# Display_Driver.net
KiCad netlist of a schematic drawn in Altium Designer
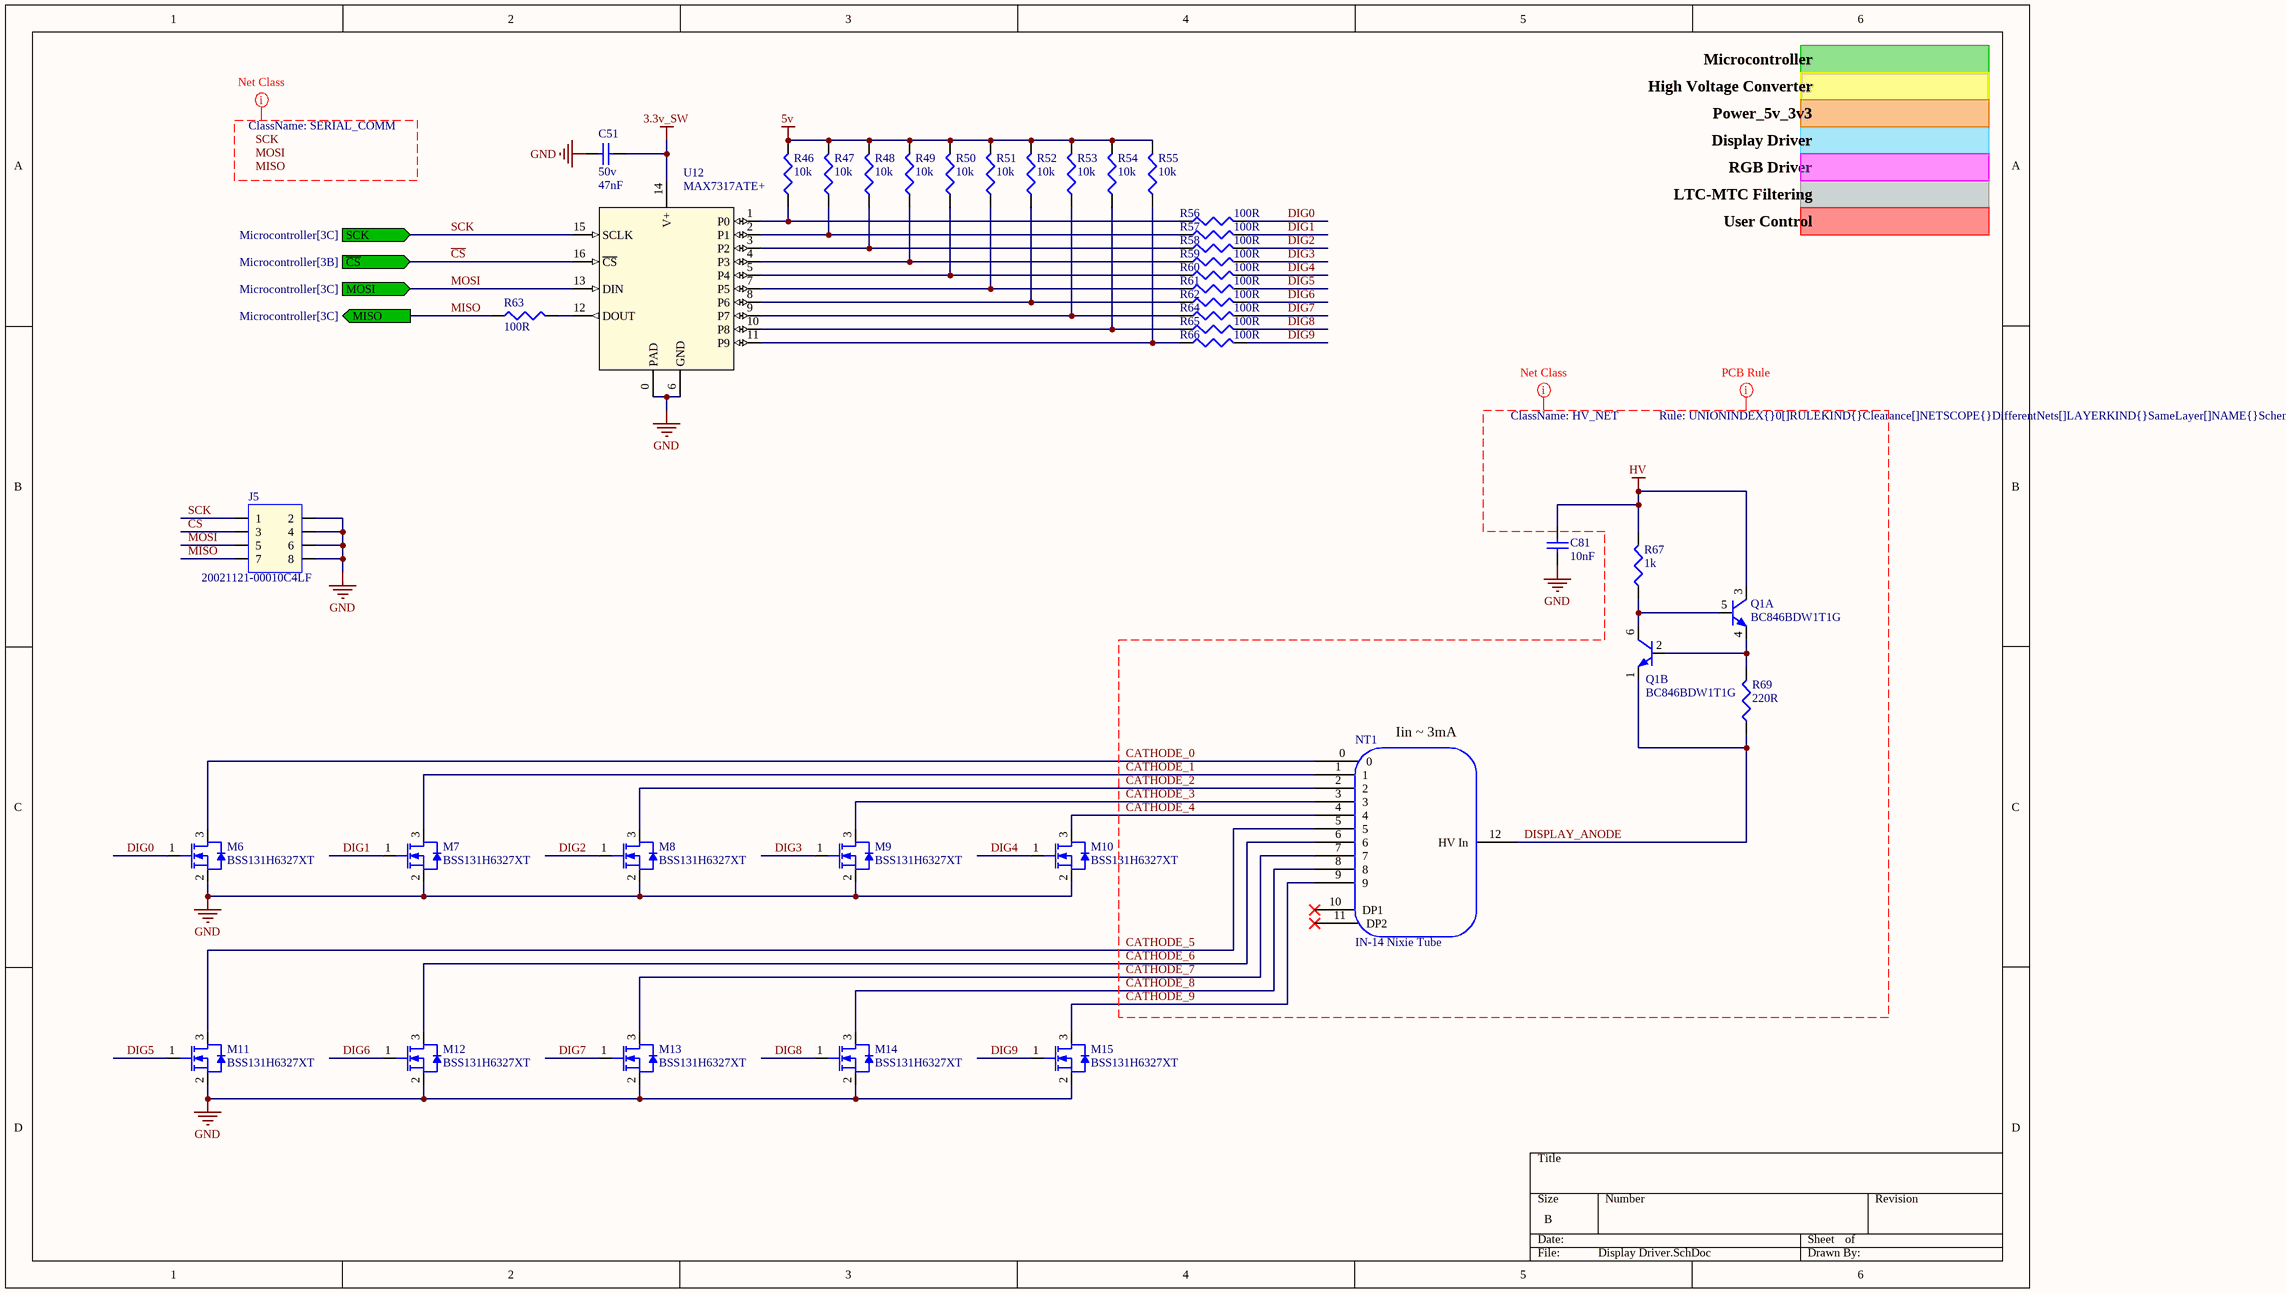
[diagram p0: Display Driver.SchDoc]

(export (version "E")
  (design (tool "Eeschema 10.0.6"))
  (components
    (comp (ref "C51")
      (value "47nF")
      (footprint "CAP0603R")
      (fields (field (name "TOLERANCE") "10%") (field (name "MFG") "VISHAY") (field (name "VOLTAGE") "50v"))
      (libsource (lib "Altium Library") (part "47nF 50v (0603)"))
    )
    (comp (ref "C81")
      (value "10nF")
      (footprint "CAP0805R")
      (fields (field (name "TOLERANCE") "10%") (field (name "MFG") "Murata") (field (name "VOLTAGE") "250v"))
      (libsource (lib "Altium Library") (part "10nF 250v (0805)"))
    )
    (comp (ref "J5")
      (value "20021121-00010C4LF")
      (footprint "2x4 SMD Header 1.27mm")
      (description "2x4 Header SMD (1.27mm)")
      (fields (field (name "MFG") "FCI"))
      (libsource (lib "Altium Library") (part "2x4 Header SMD (1.27mm)"))
    )
    (comp (ref "M6")
      (value "BSS131H6327XT")
      (footprint "SOT23-3 REFLOW")
      (description "NFET_SINGLE_100mA_240v")
      (fields (field (name "MFG") "INFINEON"))
      (libsource (lib "Altium Library") (part "BSS131H6327XT"))
    )
    (comp (ref "M7")
      (value "BSS131H6327XT")
      (footprint "SOT23-3 REFLOW")
      (description "NFET_SINGLE_100mA_240v")
      (fields (field (name "MFG") "INFINEON"))
      (libsource (lib "Altium Library") (part "BSS131H6327XT"))
    )
    (comp (ref "M8")
      (value "BSS131H6327XT")
      (footprint "SOT23-3 REFLOW")
      (description "NFET_SINGLE_100mA_240v")
      (fields (field (name "MFG") "INFINEON"))
      (libsource (lib "Altium Library") (part "BSS131H6327XT"))
    )
    (comp (ref "M9")
      (value "BSS131H6327XT")
      (footprint "SOT23-3 REFLOW")
      (description "NFET_SINGLE_100mA_240v")
      (fields (field (name "MFG") "INFINEON"))
      (libsource (lib "Altium Library") (part "BSS131H6327XT"))
    )
    (comp (ref "M10")
      (value "BSS131H6327XT")
      (footprint "SOT23-3 REFLOW")
      (description "NFET_SINGLE_100mA_240v")
      (fields (field (name "MFG") "INFINEON"))
      (libsource (lib "Altium Library") (part "BSS131H6327XT"))
    )
    (comp (ref "M11")
      (value "BSS131H6327XT")
      (footprint "SOT23-3 REFLOW")
      (description "NFET_SINGLE_100mA_240v")
      (fields (field (name "MFG") "INFINEON"))
      (libsource (lib "Altium Library") (part "BSS131H6327XT"))
    )
    (comp (ref "M12")
      (value "BSS131H6327XT")
      (footprint "SOT23-3 REFLOW")
      (description "NFET_SINGLE_100mA_240v")
      (fields (field (name "MFG") "INFINEON"))
      (libsource (lib "Altium Library") (part "BSS131H6327XT"))
    )
    (comp (ref "M13")
      (value "BSS131H6327XT")
      (footprint "SOT23-3 REFLOW")
      (description "NFET_SINGLE_100mA_240v")
      (fields (field (name "MFG") "INFINEON"))
      (libsource (lib "Altium Library") (part "BSS131H6327XT"))
    )
    (comp (ref "M14")
      (value "BSS131H6327XT")
      (footprint "SOT23-3 REFLOW")
      (description "NFET_SINGLE_100mA_240v")
      (fields (field (name "MFG") "INFINEON"))
      (libsource (lib "Altium Library") (part "BSS131H6327XT"))
    )
    (comp (ref "M15")
      (value "BSS131H6327XT")
      (footprint "SOT23-3 REFLOW")
      (description "NFET_SINGLE_100mA_240v")
      (fields (field (name "MFG") "INFINEON"))
      (libsource (lib "Altium Library") (part "BSS131H6327XT"))
    )
    (comp (ref "NT1")
      (value "IN-14 Nixie Tube")
      (footprint "IN-14 Nixie Tube")
      (libsource (lib "Altium Library") (part "IN-14 Nixie Tube"))
    )
    (comp (ref "Q1")
      (value "BC846BDW1T1G")
      (footprint "SC70")
      (description "BJT, Dual NPN, 65v, 100mA")
      (fields (field (name "MFG") "ON Semiconductor"))
      (libsource (lib "Altium Library") (part "BC846BDW1T1G"))
    )
    (comp (ref "R46")
      (value "10k")
      (footprint "RES0402R")
      (fields (field (name "TOLERANCE") "1%") (field (name "POWER") "63mW") (field (name "MFG") "Vishay"))
      (libsource (lib "Altium Library") (part "10k (0402)"))
    )
    (comp (ref "R47")
      (value "10k")
      (footprint "RES0402R")
      (fields (field (name "TOLERANCE") "1%") (field (name "POWER") "63mW") (field (name "MFG") "Vishay"))
      (libsource (lib "Altium Library") (part "10k (0402)"))
    )
    (comp (ref "R48")
      (value "10k")
      (footprint "RES0402R")
      (fields (field (name "TOLERANCE") "1%") (field (name "POWER") "63mW") (field (name "MFG") "Vishay"))
      (libsource (lib "Altium Library") (part "10k (0402)"))
    )
    (comp (ref "R49")
      (value "10k")
      (footprint "RES0402R")
      (fields (field (name "TOLERANCE") "1%") (field (name "POWER") "63mW") (field (name "MFG") "Vishay"))
      (libsource (lib "Altium Library") (part "10k (0402)"))
    )
    (comp (ref "R50")
      (value "10k")
      (footprint "RES0402R")
      (fields (field (name "TOLERANCE") "1%") (field (name "POWER") "63mW") (field (name "MFG") "Vishay"))
      (libsource (lib "Altium Library") (part "10k (0402)"))
    )
    (comp (ref "R51")
      (value "10k")
      (footprint "RES0402R")
      (fields (field (name "TOLERANCE") "1%") (field (name "POWER") "63mW") (field (name "MFG") "Vishay"))
      (libsource (lib "Altium Library") (part "10k (0402)"))
    )
    (comp (ref "R52")
      (value "10k")
      (footprint "RES0402R")
      (fields (field (name "TOLERANCE") "1%") (field (name "POWER") "63mW") (field (name "MFG") "Vishay"))
      (libsource (lib "Altium Library") (part "10k (0402)"))
    )
    (comp (ref "R53")
      (value "10k")
      (footprint "RES0402R")
      (fields (field (name "TOLERANCE") "1%") (field (name "POWER") "63mW") (field (name "MFG") "Vishay"))
      (libsource (lib "Altium Library") (part "10k (0402)"))
    )
    (comp (ref "R54")
      (value "10k")
      (footprint "RES0402R")
      (fields (field (name "TOLERANCE") "1%") (field (name "POWER") "63mW") (field (name "MFG") "Vishay"))
      (libsource (lib "Altium Library") (part "10k (0402)"))
    )
    (comp (ref "R55")
      (value "10k")
      (footprint "RES0402R")
      (fields (field (name "TOLERANCE") "1%") (field (name "POWER") "63mW") (field (name "MFG") "Vishay"))
      (libsource (lib "Altium Library") (part "10k (0402)"))
    )
    (comp (ref "R56")
      (value "100R")
      (footprint "RES0402R")
      (fields (field (name "TOLERANCE") "1%") (field (name "POWER") "63mW") (field (name "MFG") "Vishay"))
      (libsource (lib "Altium Library") (part "100R (0402)"))
    )
    (comp (ref "R57")
      (value "100R")
      (footprint "RES0402R")
      (fields (field (name "TOLERANCE") "1%") (field (name "POWER") "63mW") (field (name "MFG") "Vishay"))
      (libsource (lib "Altium Library") (part "100R (0402)"))
    )
    (comp (ref "R58")
      (value "100R")
      (footprint "RES0402R")
      (fields (field (name "TOLERANCE") "1%") (field (name "POWER") "63mW") (field (name "MFG") "Vishay"))
      (libsource (lib "Altium Library") (part "100R (0402)"))
    )
    (comp (ref "R59")
      (value "100R")
      (footprint "RES0402R")
      (fields (field (name "TOLERANCE") "1%") (field (name "POWER") "63mW") (field (name "MFG") "Vishay"))
      (libsource (lib "Altium Library") (part "100R (0402)"))
    )
    (comp (ref "R60")
      (value "100R")
      (footprint "RES0402R")
      (fields (field (name "TOLERANCE") "1%") (field (name "POWER") "63mW") (field (name "MFG") "Vishay"))
      (libsource (lib "Altium Library") (part "100R (0402)"))
    )
    (comp (ref "R61")
      (value "100R")
      (footprint "RES0402R")
      (fields (field (name "TOLERANCE") "1%") (field (name "POWER") "63mW") (field (name "MFG") "Vishay"))
      (libsource (lib "Altium Library") (part "100R (0402)"))
    )
    (comp (ref "R62")
      (value "100R")
      (footprint "RES0402R")
      (fields (field (name "TOLERANCE") "1%") (field (name "POWER") "63mW") (field (name "MFG") "Vishay"))
      (libsource (lib "Altium Library") (part "100R (0402)"))
    )
    (comp (ref "R63")
      (value "100R")
      (footprint "RES0402R")
      (fields (field (name "TOLERANCE") "1%") (field (name "POWER") "63mW") (field (name "MFG") "Vishay"))
      (libsource (lib "Altium Library") (part "100R (0402)"))
    )
    (comp (ref "R64")
      (value "100R")
      (footprint "RES0402R")
      (fields (field (name "TOLERANCE") "1%") (field (name "POWER") "63mW") (field (name "MFG") "Vishay"))
      (libsource (lib "Altium Library") (part "100R (0402)"))
    )
    (comp (ref "R65")
      (value "100R")
      (footprint "RES0402R")
      (fields (field (name "TOLERANCE") "1%") (field (name "POWER") "63mW") (field (name "MFG") "Vishay"))
      (libsource (lib "Altium Library") (part "100R (0402)"))
    )
    (comp (ref "R66")
      (value "100R")
      (footprint "RES0402R")
      (fields (field (name "TOLERANCE") "1%") (field (name "POWER") "63mW") (field (name "MFG") "Vishay"))
      (libsource (lib "Altium Library") (part "100R (0402)"))
    )
    (comp (ref "R67")
      (value "1k")
      (footprint "RES0402R")
      (fields (field (name "TOLERANCE") "1%") (field (name "POWER") "63mW") (field (name "MFG") "Vishay"))
      (libsource (lib "Altium Library") (part "1k (0402)"))
    )
    (comp (ref "R69")
      (value "220R")
      (footprint "RES0603R")
      (fields (field (name "TOLERANCE") "1%") (field (name "POWER") "0.1W") (field (name "MFG") "Vishay"))
      (libsource (lib "Altium Library") (part "220R (0603)"))
    )
    (comp (ref "U12")
      (value "MAX7317ATE+")
      (footprint "TQFN-16")
      (description "Port Expander, 10-bit, SPI")
      (fields (field (name "MFG") "MAXIM"))
      (libsource (lib "Altium Library") (part "MAX7317ATE+"))
    )
  )
  (nets
    (net (code "1") (name "/CATHODE_0") (class "Default")
      (node (ref "M6") (pin "3") (pinfunction "DRAIN_3") (pintype "passive"))
      (node (ref "NT1") (pin "0") (pinfunction "0_0") (pintype "passive"))
    )
    (net (code "2") (name "/CATHODE_1") (class "Default")
      (node (ref "M7") (pin "3") (pinfunction "DRAIN_3") (pintype "passive"))
      (node (ref "NT1") (pin "1") (pinfunction "1_1") (pintype "passive"))
    )
    (net (code "3") (name "/CATHODE_2") (class "Default")
      (node (ref "M8") (pin "3") (pinfunction "DRAIN_3") (pintype "passive"))
      (node (ref "NT1") (pin "2") (pinfunction "2_2") (pintype "passive"))
    )
    (net (code "4") (name "/CATHODE_3") (class "Default")
      (node (ref "M9") (pin "3") (pinfunction "DRAIN_3") (pintype "passive"))
      (node (ref "NT1") (pin "3") (pinfunction "3_3") (pintype "passive"))
    )
    (net (code "5") (name "/CATHODE_4") (class "Default")
      (node (ref "M10") (pin "3") (pinfunction "DRAIN_3") (pintype "passive"))
      (node (ref "NT1") (pin "4") (pinfunction "4_4") (pintype "passive"))
    )
    (net (code "6") (name "/CATHODE_5") (class "Default")
      (node (ref "M11") (pin "3") (pinfunction "DRAIN_3") (pintype "passive"))
      (node (ref "NT1") (pin "5") (pinfunction "5_5") (pintype "passive"))
    )
    (net (code "7") (name "/CATHODE_6") (class "Default")
      (node (ref "M12") (pin "3") (pinfunction "DRAIN_3") (pintype "passive"))
      (node (ref "NT1") (pin "6") (pinfunction "6_6") (pintype "passive"))
    )
    (net (code "8") (name "/CATHODE_7") (class "Default")
      (node (ref "M13") (pin "3") (pinfunction "DRAIN_3") (pintype "passive"))
      (node (ref "NT1") (pin "7") (pinfunction "7_7") (pintype "passive"))
    )
    (net (code "9") (name "/CATHODE_8") (class "Default")
      (node (ref "M14") (pin "3") (pinfunction "DRAIN_3") (pintype "passive"))
      (node (ref "NT1") (pin "8") (pinfunction "8_8") (pintype "passive"))
    )
    (net (code "10") (name "/CATHODE_9") (class "Default")
      (node (ref "M15") (pin "3") (pinfunction "DRAIN_3") (pintype "passive"))
      (node (ref "NT1") (pin "9") (pinfunction "9_9") (pintype "passive"))
    )
    (net (code "11") (name "/DIG0") (class "Default")
      (node (ref "M6") (pin "1") (pinfunction "GATE_1") (pintype "passive"))
      (node (ref "R56") (pin "2") (pinfunction "2_2") (pintype "passive"))
    )
    (net (code "12") (name "/DIG1") (class "Default")
      (node (ref "M7") (pin "1") (pinfunction "GATE_1") (pintype "passive"))
      (node (ref "R57") (pin "2") (pinfunction "2_2") (pintype "passive"))
    )
    (net (code "13") (name "/DIG2") (class "Default")
      (node (ref "M8") (pin "1") (pinfunction "GATE_1") (pintype "passive"))
      (node (ref "R58") (pin "2") (pinfunction "2_2") (pintype "passive"))
    )
    (net (code "14") (name "/DIG3") (class "Default")
      (node (ref "M9") (pin "1") (pinfunction "GATE_1") (pintype "passive"))
      (node (ref "R59") (pin "2") (pinfunction "2_2") (pintype "passive"))
    )
    (net (code "15") (name "/DIG4") (class "Default")
      (node (ref "M10") (pin "1") (pinfunction "GATE_1") (pintype "passive"))
      (node (ref "R60") (pin "2") (pinfunction "2_2") (pintype "passive"))
    )
    (net (code "16") (name "/DIG5") (class "Default")
      (node (ref "M11") (pin "1") (pinfunction "GATE_1") (pintype "passive"))
      (node (ref "R61") (pin "2") (pinfunction "2_2") (pintype "passive"))
    )
    (net (code "17") (name "/DIG6") (class "Default")
      (node (ref "M12") (pin "1") (pinfunction "GATE_1") (pintype "passive"))
      (node (ref "R62") (pin "2") (pinfunction "2_2") (pintype "passive"))
    )
    (net (code "18") (name "/DIG7") (class "Default")
      (node (ref "M13") (pin "1") (pinfunction "GATE_1") (pintype "passive"))
      (node (ref "R64") (pin "2") (pinfunction "2_2") (pintype "passive"))
    )
    (net (code "19") (name "/DIG8") (class "Default")
      (node (ref "M14") (pin "1") (pinfunction "GATE_1") (pintype "passive"))
      (node (ref "R65") (pin "2") (pinfunction "2_2") (pintype "passive"))
    )
    (net (code "20") (name "/DIG9") (class "Default")
      (node (ref "M15") (pin "1") (pinfunction "GATE_1") (pintype "passive"))
      (node (ref "R66") (pin "2") (pinfunction "2_2") (pintype "passive"))
    )
    (net (code "21") (name "/DISPLAY_ANODE") (class "Default")
      (node (ref "NT1") (pin "12") (pinfunction "HV_In_12") (pintype "passive"))
      (node (ref "Q1") (pin "1") (pinfunction "C2_1") (pintype "passive"))
      (node (ref "R69") (pin "1") (pinfunction "1_1") (pintype "passive"))
    )
    (net (code "22") (name "/MISO") (class "Default")
      (node (ref "J5") (pin "7") (pinfunction "7_7") (pintype "passive"))
      (node (ref "R63") (pin "1") (pinfunction "1_1") (pintype "passive"))
    )
    (net (code "23") (name "/MOSI") (class "Default")
      (node (ref "J5") (pin "5") (pinfunction "5_5") (pintype "passive"))
      (node (ref "U12") (pin "13") (pinfunction "DIN_13") (pintype "input"))
    )
    (net (code "24") (name "/SCK") (class "Default")
      (node (ref "J5") (pin "1") (pinfunction "1_1") (pintype "passive"))
      (node (ref "U12") (pin "15") (pinfunction "SCLK_15") (pintype "input"))
    )
    (net (code "25") (name "/~{CS}") (class "Default")
      (node (ref "J5") (pin "3") (pinfunction "3_3") (pintype "passive"))
      (node (ref "U12") (pin "16") (pinfunction "~{CS}_16") (pintype "input"))
    )
    (net (code "26") (name "3.3v_SW") (class "Default")
      (node (ref "C51") (pin "2") (pinfunction "2_2") (pintype "passive"))
      (node (ref "U12") (pin "14") (pinfunction "V+_14") (pintype "power_in"))
    )
    (net (code "27") (name "5v") (class "Default")
      (node (ref "R46") (pin "2") (pinfunction "2_2") (pintype "passive"))
      (node (ref "R47") (pin "2") (pinfunction "2_2") (pintype "passive"))
      (node (ref "R48") (pin "2") (pinfunction "2_2") (pintype "passive"))
      (node (ref "R49") (pin "2") (pinfunction "2_2") (pintype "passive"))
      (node (ref "R50") (pin "2") (pinfunction "2_2") (pintype "passive"))
      (node (ref "R51") (pin "2") (pinfunction "2_2") (pintype "passive"))
      (node (ref "R52") (pin "2") (pinfunction "2_2") (pintype "passive"))
      (node (ref "R53") (pin "2") (pinfunction "2_2") (pintype "passive"))
      (node (ref "R54") (pin "2") (pinfunction "2_2") (pintype "passive"))
      (node (ref "R55") (pin "2") (pinfunction "2_2") (pintype "passive"))
    )
    (net (code "28") (name "GND") (class "Default")
      (node (ref "C51") (pin "1") (pinfunction "1_1") (pintype "passive"))
      (node (ref "C81") (pin "2") (pinfunction "2_2") (pintype "passive"))
      (node (ref "J5") (pin "2") (pinfunction "2_2") (pintype "passive"))
      (node (ref "J5") (pin "4") (pinfunction "4_4") (pintype "passive"))
      (node (ref "J5") (pin "6") (pinfunction "6_6") (pintype "passive"))
      (node (ref "J5") (pin "8") (pinfunction "8_8") (pintype "passive"))
      (node (ref "M10") (pin "2") (pinfunction "SOURCE_2") (pintype "passive"))
      (node (ref "M11") (pin "2") (pinfunction "SOURCE_2") (pintype "passive"))
      (node (ref "M12") (pin "2") (pinfunction "SOURCE_2") (pintype "passive"))
      (node (ref "M13") (pin "2") (pinfunction "SOURCE_2") (pintype "passive"))
      (node (ref "M14") (pin "2") (pinfunction "SOURCE_2") (pintype "passive"))
      (node (ref "M15") (pin "2") (pinfunction "SOURCE_2") (pintype "passive"))
      (node (ref "M6") (pin "2") (pinfunction "SOURCE_2") (pintype "passive"))
      (node (ref "M7") (pin "2") (pinfunction "SOURCE_2") (pintype "passive"))
      (node (ref "M8") (pin "2") (pinfunction "SOURCE_2") (pintype "passive"))
      (node (ref "M9") (pin "2") (pinfunction "SOURCE_2") (pintype "passive"))
      (node (ref "U12") (pin "0") (pinfunction "PAD_0") (pintype "passive"))
      (node (ref "U12") (pin "6") (pinfunction "GND_6") (pintype "power_in"))
    )
    (net (code "29") (name "HV") (class "Default")
      (node (ref "C81") (pin "1") (pinfunction "1_1") (pintype "passive"))
      (node (ref "Q1") (pin "3") (pinfunction "E1_3") (pintype "passive"))
      (node (ref "R67") (pin "2") (pinfunction "2_2") (pintype "passive"))
    )
    (net (code "30") (name "Net-(Q1A-B1)") (class "Default")
      (node (ref "Q1") (pin "5") (pinfunction "B1_5") (pintype "passive"))
      (node (ref "Q1") (pin "6") (pinfunction "E2_6") (pintype "passive"))
      (node (ref "R67") (pin "1") (pinfunction "1_1") (pintype "passive"))
    )
    (net (code "31") (name "Net-(Q1A-C1)") (class "Default")
      (node (ref "Q1") (pin "2") (pinfunction "B2_2") (pintype "passive"))
      (node (ref "Q1") (pin "4") (pinfunction "C1_4") (pintype "passive"))
      (node (ref "R69") (pin "2") (pinfunction "2_2") (pintype "passive"))
    )
    (net (code "32") (name "Net-(U12-DOUT)") (class "Default")
      (node (ref "R63") (pin "2") (pinfunction "2_2") (pintype "passive"))
      (node (ref "U12") (pin "12") (pinfunction "DOUT_12") (pintype "output"))
    )
    (net (code "33") (name "Net-(U12-P0)") (class "Default")
      (node (ref "R46") (pin "1") (pinfunction "1_1") (pintype "passive"))
      (node (ref "R56") (pin "1") (pinfunction "1_1") (pintype "passive"))
      (node (ref "U12") (pin "1") (pinfunction "P0_1") (pintype "bidirectional"))
    )
    (net (code "34") (name "Net-(U12-P1)") (class "Default")
      (node (ref "R47") (pin "1") (pinfunction "1_1") (pintype "passive"))
      (node (ref "R57") (pin "1") (pinfunction "1_1") (pintype "passive"))
      (node (ref "U12") (pin "2") (pinfunction "P1_2") (pintype "bidirectional"))
    )
    (net (code "35") (name "Net-(U12-P2)") (class "Default")
      (node (ref "R48") (pin "1") (pinfunction "1_1") (pintype "passive"))
      (node (ref "R58") (pin "1") (pinfunction "1_1") (pintype "passive"))
      (node (ref "U12") (pin "3") (pinfunction "P2_3") (pintype "bidirectional"))
    )
    (net (code "36") (name "Net-(U12-P3)") (class "Default")
      (node (ref "R49") (pin "1") (pinfunction "1_1") (pintype "passive"))
      (node (ref "R59") (pin "1") (pinfunction "1_1") (pintype "passive"))
      (node (ref "U12") (pin "4") (pinfunction "P3_4") (pintype "bidirectional"))
    )
    (net (code "37") (name "Net-(U12-P4)") (class "Default")
      (node (ref "R50") (pin "1") (pinfunction "1_1") (pintype "passive"))
      (node (ref "R60") (pin "1") (pinfunction "1_1") (pintype "passive"))
      (node (ref "U12") (pin "5") (pinfunction "P4_5") (pintype "bidirectional"))
    )
    (net (code "38") (name "Net-(U12-P5)") (class "Default")
      (node (ref "R51") (pin "1") (pinfunction "1_1") (pintype "passive"))
      (node (ref "R61") (pin "1") (pinfunction "1_1") (pintype "passive"))
      (node (ref "U12") (pin "7") (pinfunction "P5_7") (pintype "bidirectional"))
    )
    (net (code "39") (name "Net-(U12-P6)") (class "Default")
      (node (ref "R52") (pin "1") (pinfunction "1_1") (pintype "passive"))
      (node (ref "R62") (pin "1") (pinfunction "1_1") (pintype "passive"))
      (node (ref "U12") (pin "8") (pinfunction "P6_8") (pintype "bidirectional"))
    )
    (net (code "40") (name "Net-(U12-P7)") (class "Default")
      (node (ref "R53") (pin "1") (pinfunction "1_1") (pintype "passive"))
      (node (ref "R64") (pin "1") (pinfunction "1_1") (pintype "passive"))
      (node (ref "U12") (pin "9") (pinfunction "P7_9") (pintype "bidirectional"))
    )
    (net (code "41") (name "Net-(U12-P8)") (class "Default")
      (node (ref "R54") (pin "1") (pinfunction "1_1") (pintype "passive"))
      (node (ref "R65") (pin "1") (pinfunction "1_1") (pintype "passive"))
      (node (ref "U12") (pin "10") (pinfunction "P8_10") (pintype "bidirectional"))
    )
    (net (code "42") (name "Net-(U12-P9)") (class "Default")
      (node (ref "R55") (pin "1") (pinfunction "1_1") (pintype "passive"))
      (node (ref "R66") (pin "1") (pinfunction "1_1") (pintype "passive"))
      (node (ref "U12") (pin "11") (pinfunction "P9_11") (pintype "bidirectional"))
    )
    (net (code "43") (name "unconnected-(NT1-DP1-Pad10)") (class "Default")
      (node (ref "NT1") (pin "10") (pinfunction "DP1_10") (pintype "passive+no_connect"))
    )
    (net (code "44") (name "unconnected-(NT1-DP2-Pad11)") (class "Default")
      (node (ref "NT1") (pin "11") (pinfunction "DP2_11") (pintype "passive+no_connect"))
    )
  )
)
